# LoRa_Transceiver.net
KiCad netlist of a schematic drawn in Altium Designer
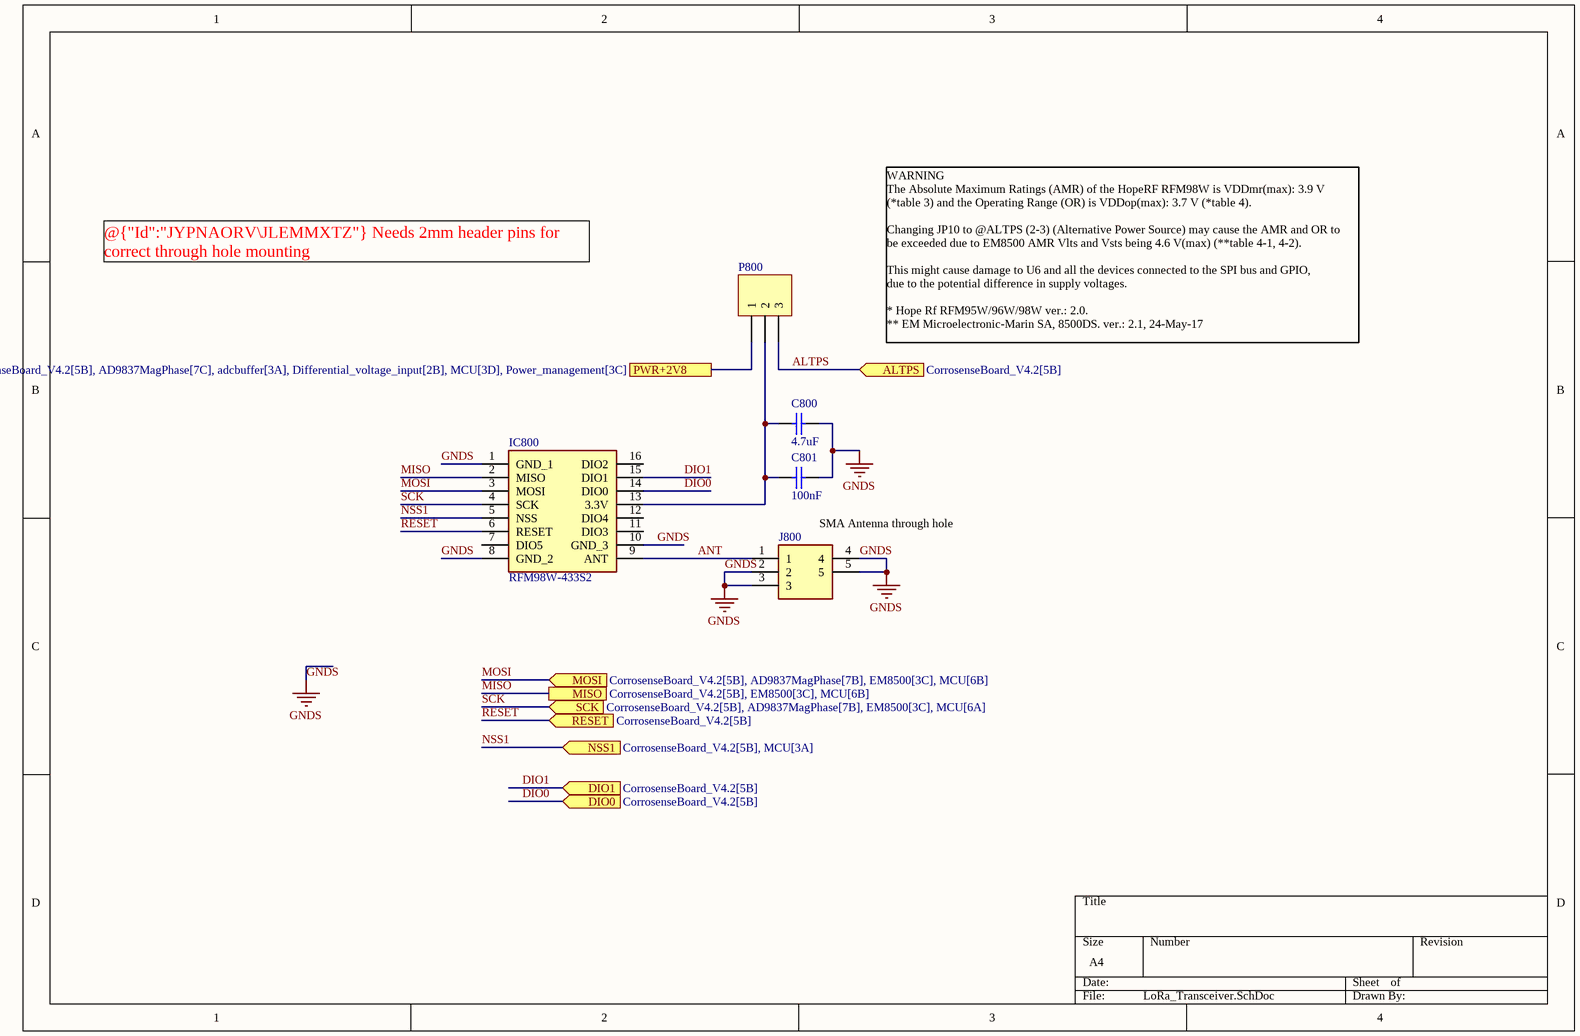
[diagram p0: LoRa_Transceiver.SchDoc]

(export (version "E")
  (design (tool "Eeschema 10.0.6"))
  (components
    (comp (ref "C800")
      (value "4.7uF")
      (footprint "1608[0603]")
      (description "CAP CER 25V X7R 0603")
      (fields (field (name "TOLERANCE") "±10%") (field (name "MANUFACTURER") "Murata Electronics"))
      (libsource (lib "Miscellaneous Devices") (part "Cap"))
    )
    (comp (ref "C801")
      (value "100nF")
      (footprint "1608[0603]")
      (description "CAP CER 25V X7R 0603")
      (fields (field (name "TOLERANCE") "±10%") (field (name "MANUFACTURER") "Murata Electronics"))
      (libsource (lib "Miscellaneous Devices") (part "Cap"))
    )
    (comp (ref "IC800")
      (value "RFM98W-433S2")
      (footprint "RFM98W433S2")
      (description "Integrated Circuit")
      (fields
        (field (name "MOUSER PART NUMBER") "223-RFM98W-433S2")
        (field (name "MANUFACTURER") "RF SOLUTIONS")
      )
      (libsource (lib "*") (part "RFM98W-433S2"))
    )
    (comp (ref "J800")
      (value "0733910070")
      (footprint "733910070")
      (description "Connector")
      (fields (field (name "MANUFACTURER") "Molex") (field (name "MPN") "73391-0070"))
      (libsource (lib "*") (part "0733910070"))
    )
    (comp (ref "P800")
      (value "Header, 3-Pin")
      (footprint "HDR1X3")
      (fields
        (field (name "MANUFACTURER") "Wurth Elektronik")
        (field (name "MPN") "61300311121")
        (field (name "PUBLISHER") "Altium Limited")
      )
      (libsource (lib "Miscellaneous Connectors") (part "Header 3"))
    )
  )
  (nets
    (net (code "1") (name "/ALTPS") (class "Default")
      (node (ref "P800") (pin "3") (pinfunction "3_3") (pintype "passive"))
    )
    (net (code "2") (name "/ANT") (class "Default")
      (node (ref "IC800") (pin "9") (pinfunction "ANT_9") (pintype "passive"))
      (node (ref "J800") (pin "1") (pinfunction "1_1") (pintype "passive"))
    )
    (net (code "3") (name "/DIO0") (class "Default")
      (node (ref "IC800") (pin "14") (pinfunction "DIO0_14") (pintype "passive"))
    )
    (net (code "4") (name "/DIO1") (class "Default")
      (node (ref "IC800") (pin "15") (pinfunction "DIO1_15") (pintype "passive"))
    )
    (net (code "5") (name "/MISO") (class "Default")
      (node (ref "IC800") (pin "2") (pinfunction "MISO_2") (pintype "passive"))
    )
    (net (code "6") (name "/MOSI") (class "Default")
      (node (ref "IC800") (pin "3") (pinfunction "MOSI_3") (pintype "passive"))
    )
    (net (code "7") (name "/NSS1") (class "Default")
      (node (ref "IC800") (pin "5") (pinfunction "NSS_5") (pintype "passive"))
    )
    (net (code "8") (name "/PWR+2V8") (class "Default")
      (node (ref "P800") (pin "1") (pinfunction "1_1") (pintype "passive"))
    )
    (net (code "9") (name "/RESET") (class "Default")
      (node (ref "IC800") (pin "6") (pinfunction "RESET_6") (pintype "passive"))
    )
    (net (code "10") (name "/SCK") (class "Default")
      (node (ref "IC800") (pin "4") (pinfunction "SCK_4") (pintype "passive"))
    )
    (net (code "11") (name "GNDS") (class "Default")
      (node (ref "C800") (pin "1") (pinfunction "1_1") (pintype "passive"))
      (node (ref "C801") (pin "1") (pinfunction "1_1") (pintype "passive"))
      (node (ref "IC800") (pin "1") (pinfunction "GND_1_1") (pintype "passive"))
      (node (ref "IC800") (pin "10") (pinfunction "GND_3_10") (pintype "passive"))
      (node (ref "IC800") (pin "8") (pinfunction "GND_2_8") (pintype "passive"))
      (node (ref "J800") (pin "2") (pinfunction "2_2") (pintype "passive"))
      (node (ref "J800") (pin "3") (pinfunction "3_3") (pintype "passive"))
      (node (ref "J800") (pin "4") (pinfunction "4_4") (pintype "passive"))
      (node (ref "J800") (pin "5") (pinfunction "5_5") (pintype "passive"))
    )
    (net (code "12") (name "Net-(IC800-3.3V)") (class "Default")
      (node (ref "C800") (pin "2") (pinfunction "2_2") (pintype "passive"))
      (node (ref "C801") (pin "2") (pinfunction "2_2") (pintype "passive"))
      (node (ref "IC800") (pin "13") (pinfunction "3.3V_13") (pintype "passive"))
      (node (ref "P800") (pin "2") (pinfunction "2_2") (pintype "passive"))
    )
    (net (code "13") (name "unconnected-(IC800-DIO2-Pad16)") (class "Default")
      (node (ref "IC800") (pin "16") (pinfunction "DIO2_16") (pintype "passive"))
    )
    (net (code "14") (name "unconnected-(IC800-DIO3-Pad11)") (class "Default")
      (node (ref "IC800") (pin "11") (pinfunction "DIO3_11") (pintype "passive"))
    )
    (net (code "15") (name "unconnected-(IC800-DIO4-Pad12)") (class "Default")
      (node (ref "IC800") (pin "12") (pinfunction "DIO4_12") (pintype "passive"))
    )
    (net (code "16") (name "unconnected-(IC800-DIO5-Pad7)") (class "Default")
      (node (ref "IC800") (pin "7") (pinfunction "DIO5_7") (pintype "passive"))
    )
  )
)
